# Sheet_1_2024-01-01_1.net
KiCad netlist of a schematic drawn in Altium Designer
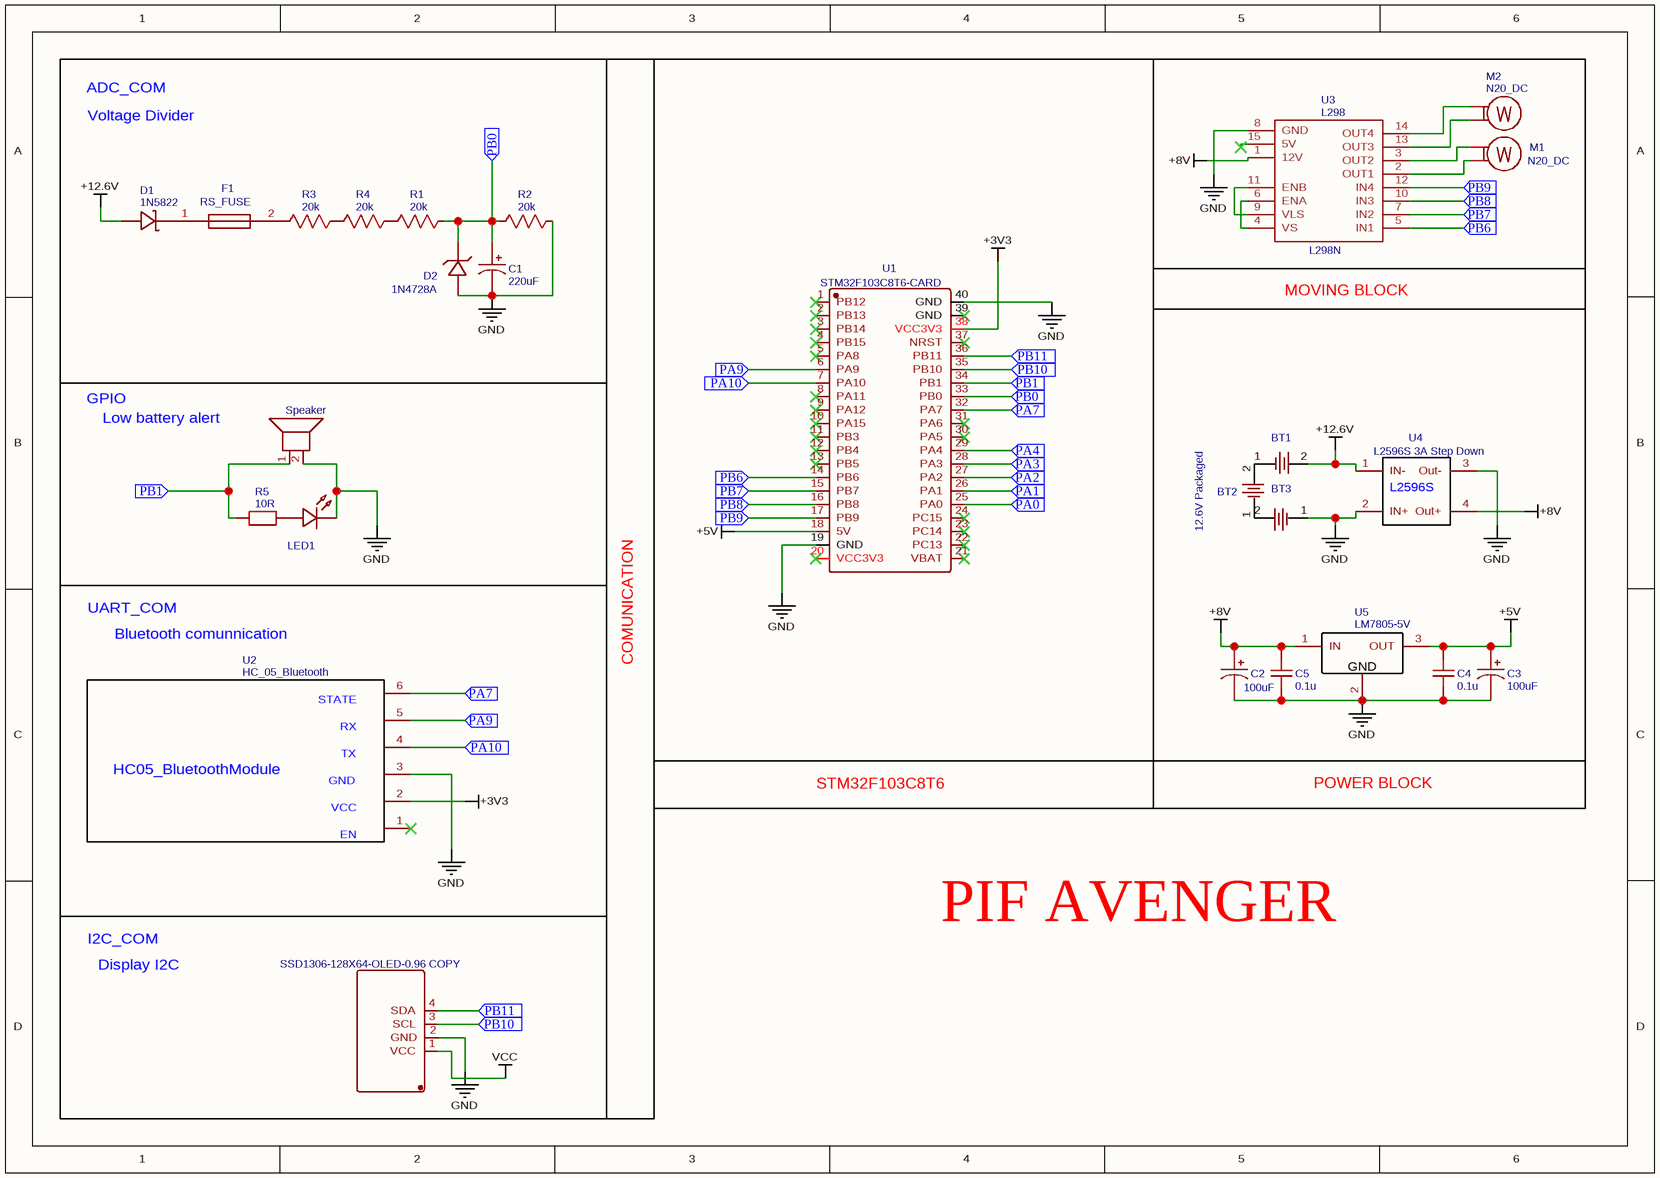
[diagram p0: Sheet_1_2024-01-01 (1).schdoc]

(export (version "E")
  (design (tool "Eeschema 10.0.6"))
  (components
    (comp (ref "BT1")
      (value "BH-18650-A1AJ006")
      (fields (field (name "MANUFACTURER") "MYOUNG(美阳)") (field (name "CONTRIBUTOR") "lcsc"))
      (libsource (lib "altium-import") (part "root_0_BH-18650-A1AJ006_"))
    )
    (comp (ref "BT2")
      (value "12.6V Packaged")
      (fields
        (field (name "MANUFACTURER") "MYOUNG(美阳)")
        (field (name "MANUFACTURER PART") "BH-18650-A1AJ006")
        (field (name "CONTRIBUTOR") "lcsc")
      )
      (libsource (lib "altium-import") (part "root_3_12.6V Packaged_"))
    )
    (comp (ref "BT3")
      (value "BH-18650-A1AJ006")
      (fields (field (name "MANUFACTURER") "MYOUNG(美阳)") (field (name "CONTRIBUTOR") "lcsc"))
      (libsource (lib "altium-import") (part "root_2_BH-18650-A1AJ006_"))
    )
    (comp (ref "C1")
      (value "220uF")
      (fields (field (name "CONTRIBUTOR") "LCEDA_Lib"))
      (libsource (lib "altium-import") (part "root_3_220uF_"))
    )
    (comp (ref "C2")
      (value "100uF")
      (fields (field (name "CONTRIBUTOR") "LCEDA_Lib"))
      (libsource (lib "altium-import") (part "root_3_100uF_"))
    )
    (comp (ref "C3")
      (value "100uF")
      (fields (field (name "CONTRIBUTOR") "LCEDA_Lib"))
      (libsource (lib "altium-import") (part "root_3_100uF_"))
    )
    (comp (ref "C4")
      (value "0.1u")
      (fields (field (name "CONTRIBUTOR") "LCEDA_Lib"))
      (libsource (lib "altium-import") (part "root_1_0.1u_"))
    )
    (comp (ref "C5")
      (value "0.1u")
      (fields (field (name "CONTRIBUTOR") "LCEDA_Lib"))
      (libsource (lib "altium-import") (part "root_1_0.1u_"))
    )
    (comp (ref "D1")
      (value "1N5822")
      (fields (field (name "MANUFACTURER") "MDD"))
      (libsource (lib "altium-import") (part "root_0_1N5822_"))
    )
    (comp (ref "D2")
      (value "1N4728A")
      (fields (field (name "MANUFACTURER") "onsemi(安森美)") (field (name "CONTRIBUTOR") "LCSC"))
      (libsource (lib "altium-import") (part "root_3_1N4728A_"))
    )
    (comp (ref "F1")
      (value "RS_FUSE")
      (fields (field (name "MANUFACTURER PART") "ResettableFuse-500mA") (field (name "CONTRIBUTOR") "LCSC"))
      (libsource (lib "altium-import") (part "root_0_RS_FUSE_"))
    )
    (comp (ref "LED1")
      (value "LED-0603_R")
      (fields
        (field (name "MANUFACTURER") "EVERLIGHT(台湾亿光)")
        (field (name "MANUFACTURER PART") "19-217/R6C-AL1M2VY/3T")
        (field (name "CONTRIBUTOR") "LCEDA_01")
      )
      (libsource (lib "altium-import") (part "root_0_LED-0603_R_"))
    )
    (comp (ref "LS1")
      (value "Speaker")
      (fields (field (name "CONTRIBUTOR") "virtualgt"))
      (libsource (lib "altium-import") (part "root_1_Speaker_"))
    )
    (comp (ref "M1")
      (value "N20_DC")
      (fields (field (name "CONTRIBUTOR") "crypt-pcb"))
      (libsource (lib "altium-import") (part "root_1_N20_DC_"))
    )
    (comp (ref "M2")
      (value "N20_DC")
      (fields (field (name "CONTRIBUTOR") "crypt-pcb"))
      (libsource (lib "altium-import") (part "root_1_N20_DC_"))
    )
    (comp (ref "PCB1")
      (value "SSD1306-128X64-OLED-0.96 COPY")
      (libsource (lib "altium-import") (part "root_2_SSD1306-128X64-OLED-0.96 COPY_"))
    )
    (comp (ref "R1")
      (value "20k")
      (fields (field (name "CONTRIBUTOR") "LCEDA_Lib"))
      (libsource (lib "altium-import") (part "root_0_20k_"))
    )
    (comp (ref "R2")
      (value "20k")
      (fields (field (name "CONTRIBUTOR") "LCEDA_Lib"))
      (libsource (lib "altium-import") (part "root_0_20k_"))
    )
    (comp (ref "R3")
      (value "20k")
      (fields (field (name "CONTRIBUTOR") "LCEDA_Lib"))
      (libsource (lib "altium-import") (part "root_0_20k_"))
    )
    (comp (ref "R4")
      (value "20k")
      (fields (field (name "CONTRIBUTOR") "LCEDA_Lib"))
      (libsource (lib "altium-import") (part "root_0_20k_"))
    )
    (comp (ref "R5")
      (value "10R")
      (fields (field (name "CONTRIBUTOR") "LCEDA_Lib"))
      (libsource (lib "altium-import") (part "root_0_10R_"))
    )
    (comp (ref "U1")
      (value "STM32F103C8T6-CARD")
      (fields (field (name "MANUFACTURER PART") "STM32F103C8T6-Card") (field (name "CONTRIBUTOR") "lcsc"))
      (libsource (lib "altium-import") (part "root_0_STM32F103C8T6-CARD_"))
    )
    (comp (ref "U2")
      (value "HC_05_Bluetooth")
      (fields (field (name "CONTRIBUTOR") "Crypt-PCB"))
      (libsource (lib "altium-import") (part "root_1_HC_05_Bluetooth_"))
    )
    (comp (ref "U3")
      (value "L298")
      (fields
        (field (name "MANUFACTURER PART") "L298N Driver")
        (field (name "CONTRIBUTOR") "huynhthienphu2492001")
      )
      (libsource (lib "altium-import") (part "root_2_L298_"))
    )
    (comp (ref "U4")
      (value "L2596S 3A Step Down")
      (fields (field (name "CONTRIBUTOR") "St1fT"))
      (libsource (lib "altium-import") (part "root_0_L2596S 3A Step Down_"))
    )
    (comp (ref "U5")
      (value "LM7805-5V")
      (fields (field (name "CONTRIBUTOR") "LCSC"))
      (libsource (lib "altium-import") (part "root_0_LM7805-5V_"))
    )
  )
  (nets
    (net (code "1") (name "+3V3") (class "Default")
      (node (ref "U1") (pin "38") (pinfunction "VCC3V3_38") (pintype "passive"))
      (node (ref "U2") (pin "2") (pinfunction "2_2") (pintype "passive"))
    )
    (net (code "2") (name "+5V") (class "Default")
      (node (ref "C3") (pin "1") (pinfunction "1_1") (pintype "passive"))
      (node (ref "C4") (pin "2") (pinfunction "2_2") (pintype "passive"))
      (node (ref "U1") (pin "18") (pinfunction "5V_18") (pintype "passive"))
      (node (ref "U5") (pin "3") (pinfunction "OUT_3") (pintype "passive"))
    )
    (net (code "3") (name "+8V") (class "Default")
      (node (ref "C2") (pin "1") (pinfunction "1_1") (pintype "passive"))
      (node (ref "C5") (pin "2") (pinfunction "2_2") (pintype "passive"))
      (node (ref "U3") (pin "1") (pinfunction "12V_1") (pintype "passive"))
      (node (ref "U4") (pin "4") (pinfunction "Out+_4") (pintype "passive"))
      (node (ref "U5") (pin "1") (pinfunction "IN_1") (pintype "passive"))
    )
    (net (code "4") (name "+12.6V") (class "Default")
      (node (ref "BT1") (pin "2") (pinfunction "2_2") (pintype "passive"))
      (node (ref "D1") (pin "1") (pinfunction "A_1") (pintype "passive"))
      (node (ref "U4") (pin "1") (pinfunction "IN-_1") (pintype "passive"))
    )
    (net (code "5") (name "/PA0") (class "Default")
      (node (ref "U1") (pin "25") (pinfunction "PA0_25") (pintype "passive"))
    )
    (net (code "6") (name "/PA1") (class "Default")
      (node (ref "U1") (pin "26") (pinfunction "PA1_26") (pintype "passive"))
    )
    (net (code "7") (name "/PA2") (class "Default")
      (node (ref "U1") (pin "27") (pinfunction "PA2_27") (pintype "passive"))
    )
    (net (code "8") (name "/PA3") (class "Default")
      (node (ref "U1") (pin "28") (pinfunction "PA3_28") (pintype "passive"))
    )
    (net (code "9") (name "/PA4") (class "Default")
      (node (ref "U1") (pin "29") (pinfunction "PA4_29") (pintype "passive"))
    )
    (net (code "10") (name "/PA7") (class "Default")
      (node (ref "U1") (pin "32") (pinfunction "PA7_32") (pintype "passive"))
      (node (ref "U2") (pin "6") (pinfunction "6_6") (pintype "passive"))
    )
    (net (code "11") (name "/PA9") (class "Default")
      (node (ref "U1") (pin "6") (pinfunction "PA9_6") (pintype "passive"))
      (node (ref "U2") (pin "5") (pinfunction "5_5") (pintype "passive"))
    )
    (net (code "12") (name "/PA10") (class "Default")
      (node (ref "U1") (pin "7") (pinfunction "PA10_7") (pintype "passive"))
      (node (ref "U2") (pin "4") (pinfunction "4_4") (pintype "passive"))
    )
    (net (code "13") (name "/PB0") (class "Default")
      (node (ref "C1") (pin "1") (pinfunction "1_1") (pintype "passive"))
      (node (ref "D2") (pin "1") (pinfunction "K_1") (pintype "passive"))
      (node (ref "R1") (pin "2") (pinfunction "2_2") (pintype "passive"))
      (node (ref "R2") (pin "1") (pinfunction "1_1") (pintype "passive"))
      (node (ref "U1") (pin "33") (pinfunction "PB0_33") (pintype "passive"))
    )
    (net (code "14") (name "/PB1") (class "Default")
      (node (ref "LS1") (pin "1") (pinfunction "1_1") (pintype "passive"))
      (node (ref "R5") (pin "1") (pinfunction "1_1") (pintype "passive"))
      (node (ref "U1") (pin "34") (pinfunction "PB1_34") (pintype "passive"))
    )
    (net (code "15") (name "/PB6") (class "Default")
      (node (ref "U1") (pin "14") (pinfunction "PB6_14") (pintype "passive"))
      (node (ref "U3") (pin "5") (pinfunction "IN1_5") (pintype "passive"))
    )
    (net (code "16") (name "/PB7") (class "Default")
      (node (ref "U1") (pin "15") (pinfunction "PB7_15") (pintype "passive"))
      (node (ref "U3") (pin "7") (pinfunction "IN2_7") (pintype "passive"))
    )
    (net (code "17") (name "/PB8") (class "Default")
      (node (ref "U1") (pin "16") (pinfunction "PB8_16") (pintype "passive"))
      (node (ref "U3") (pin "10") (pinfunction "IN3_10") (pintype "passive"))
    )
    (net (code "18") (name "/PB9") (class "Default")
      (node (ref "U1") (pin "17") (pinfunction "PB9_17") (pintype "passive"))
      (node (ref "U3") (pin "12") (pinfunction "IN4_12") (pintype "passive"))
    )
    (net (code "19") (name "/PB10") (class "Default")
      (node (ref "PCB1") (pin "3") (pinfunction "SCL_3") (pintype "passive"))
      (node (ref "U1") (pin "35") (pinfunction "PB10_35") (pintype "passive"))
    )
    (net (code "20") (name "/PB11") (class "Default")
      (node (ref "PCB1") (pin "4") (pinfunction "SDA_4") (pintype "passive"))
      (node (ref "U1") (pin "36") (pinfunction "PB11_36") (pintype "passive"))
    )
    (net (code "21") (name "GND") (class "Default")
      (node (ref "BT3") (pin "1") (pinfunction "1_1") (pintype "passive"))
      (node (ref "C1") (pin "2") (pinfunction "2_2") (pintype "passive"))
      (node (ref "C2") (pin "2") (pinfunction "2_2") (pintype "passive"))
      (node (ref "C3") (pin "2") (pinfunction "2_2") (pintype "passive"))
      (node (ref "C4") (pin "1") (pinfunction "1_1") (pintype "passive"))
      (node (ref "C5") (pin "1") (pinfunction "1_1") (pintype "passive"))
      (node (ref "D2") (pin "2") (pinfunction "A_2") (pintype "passive"))
      (node (ref "LED1") (pin "2") (pinfunction "2_2") (pintype "passive"))
      (node (ref "LS1") (pin "2") (pinfunction "2_2") (pintype "passive"))
      (node (ref "PCB1") (pin "2") (pinfunction "GND_2") (pintype "passive"))
      (node (ref "R2") (pin "2") (pinfunction "2_2") (pintype "passive"))
      (node (ref "U1") (pin "19") (pinfunction "GND_19") (pintype "passive"))
      (node (ref "U1") (pin "40") (pinfunction "GND_40") (pintype "passive"))
      (node (ref "U2") (pin "3") (pinfunction "3_3") (pintype "passive"))
      (node (ref "U3") (pin "8") (pinfunction "GND_8") (pintype "passive"))
      (node (ref "U4") (pin "2") (pinfunction "IN+_2") (pintype "passive"))
      (node (ref "U4") (pin "3") (pinfunction "Out-_3") (pintype "passive"))
      (node (ref "U5") (pin "2") (pinfunction "GND_2") (pintype "passive"))
    )
    (net (code "22") (name "Net-(BT1-Pad1)") (class "Default")
      (node (ref "BT1") (pin "1") (pinfunction "1_1") (pintype "passive"))
      (node (ref "BT2") (pin "2") (pinfunction "2_2") (pintype "passive"))
    )
    (net (code "23") (name "Net-(BT2-Pad1)") (class "Default")
      (node (ref "BT2") (pin "1") (pinfunction "1_1") (pintype "passive"))
      (node (ref "BT3") (pin "2") (pinfunction "2_2") (pintype "passive"))
    )
    (net (code "24") (name "Net-(D1-K)") (class "Default")
      (node (ref "D1") (pin "2") (pinfunction "K_2") (pintype "passive"))
      (node (ref "F1") (pin "1") (pinfunction "1_1") (pintype "passive"))
    )
    (net (code "25") (name "Net-(F1-Pad2)") (class "Default")
      (node (ref "F1") (pin "2") (pinfunction "2_2") (pintype "passive"))
      (node (ref "R3") (pin "1") (pinfunction "1_1") (pintype "passive"))
    )
    (net (code "26") (name "Net-(M1-+)") (class "Default")
      (node (ref "M1") (pin "2") (pinfunction "+_2") (pintype "passive"))
      (node (ref "U3") (pin "2") (pinfunction "OUT1_2") (pintype "passive"))
    )
    (net (code "27") (name "Net-(M1--)") (class "Default")
      (node (ref "M1") (pin "1") (pinfunction "-_1") (pintype "passive"))
      (node (ref "U3") (pin "3") (pinfunction "OUT2_3") (pintype "passive"))
    )
    (net (code "28") (name "Net-(M2-+)") (class "Default")
      (node (ref "M2") (pin "2") (pinfunction "+_2") (pintype "passive"))
      (node (ref "U3") (pin "13") (pinfunction "OUT3_13") (pintype "passive"))
    )
    (net (code "29") (name "Net-(M2--)") (class "Default")
      (node (ref "M2") (pin "1") (pinfunction "-_1") (pintype "passive"))
      (node (ref "U3") (pin "14") (pinfunction "OUT4_14") (pintype "passive"))
    )
    (net (code "30") (name "Net-(R1-Pad1)") (class "Default")
      (node (ref "R1") (pin "1") (pinfunction "1_1") (pintype "passive"))
      (node (ref "R4") (pin "2") (pinfunction "2_2") (pintype "passive"))
    )
    (net (code "31") (name "Net-(R3-Pad2)") (class "Default")
      (node (ref "R3") (pin "2") (pinfunction "2_2") (pintype "passive"))
      (node (ref "R4") (pin "1") (pinfunction "1_1") (pintype "passive"))
    )
    (net (code "32") (name "Net-(U3-ENA)") (class "Default")
      (node (ref "U3") (pin "4") (pinfunction "VS_4") (pintype "passive"))
      (node (ref "U3") (pin "6") (pinfunction "ENA_6") (pintype "passive"))
    )
    (net (code "33") (name "Net-(U3-ENB)") (class "Default")
      (node (ref "U3") (pin "11") (pinfunction "ENB_11") (pintype "passive"))
      (node (ref "U3") (pin "9") (pinfunction "VLS_9") (pintype "passive"))
    )
    (net (code "34") (name "VCC") (class "Default")
      (node (ref "PCB1") (pin "1") (pinfunction "VCC_1") (pintype "passive"))
    )
    (net (code "35") (name "unconnected-(LED1-Pad1)") (class "Default")
      (node (ref "LED1") (pin "1") (pinfunction "1_1") (pintype "passive"))
    )
    (net (code "36") (name "unconnected-(R5-Pad2)") (class "Default")
      (node (ref "R5") (pin "2") (pinfunction "2_2") (pintype "passive"))
    )
    (net (code "37") (name "unconnected-(U1-GND-Pad39)") (class "Default")
      (node (ref "U1") (pin "39") (pinfunction "GND_39") (pintype "passive+no_connect"))
    )
    (net (code "38") (name "unconnected-(U1-NRST-Pad37)") (class "Default")
      (node (ref "U1") (pin "37") (pinfunction "NRST_37") (pintype "passive+no_connect"))
    )
    (net (code "39") (name "unconnected-(U1-PA5-Pad30)") (class "Default")
      (node (ref "U1") (pin "30") (pinfunction "PA5_30") (pintype "passive+no_connect"))
    )
    (net (code "40") (name "unconnected-(U1-PA6-Pad31)") (class "Default")
      (node (ref "U1") (pin "31") (pinfunction "PA6_31") (pintype "passive+no_connect"))
    )
    (net (code "41") (name "unconnected-(U1-PA8-Pad5)") (class "Default")
      (node (ref "U1") (pin "5") (pinfunction "PA8_5") (pintype "passive+no_connect"))
    )
    (net (code "42") (name "unconnected-(U1-PA11-Pad8)") (class "Default")
      (node (ref "U1") (pin "8") (pinfunction "PA11_8") (pintype "passive+no_connect"))
    )
    (net (code "43") (name "unconnected-(U1-PA12-Pad9)") (class "Default")
      (node (ref "U1") (pin "9") (pinfunction "PA12_9") (pintype "passive+no_connect"))
    )
    (net (code "44") (name "unconnected-(U1-PA15-Pad10)") (class "Default")
      (node (ref "U1") (pin "10") (pinfunction "PA15_10") (pintype "passive+no_connect"))
    )
    (net (code "45") (name "unconnected-(U1-PB3-Pad11)") (class "Default")
      (node (ref "U1") (pin "11") (pinfunction "PB3_11") (pintype "passive+no_connect"))
    )
    (net (code "46") (name "unconnected-(U1-PB4-Pad12)") (class "Default")
      (node (ref "U1") (pin "12") (pinfunction "PB4_12") (pintype "passive+no_connect"))
    )
    (net (code "47") (name "unconnected-(U1-PB5-Pad13)") (class "Default")
      (node (ref "U1") (pin "13") (pinfunction "PB5_13") (pintype "passive+no_connect"))
    )
    (net (code "48") (name "unconnected-(U1-PB12-Pad1)") (class "Default")
      (node (ref "U1") (pin "1") (pinfunction "PB12_1") (pintype "passive+no_connect"))
    )
    (net (code "49") (name "unconnected-(U1-PB13-Pad2)") (class "Default")
      (node (ref "U1") (pin "2") (pinfunction "PB13_2") (pintype "passive+no_connect"))
    )
    (net (code "50") (name "unconnected-(U1-PB14-Pad3)") (class "Default")
      (node (ref "U1") (pin "3") (pinfunction "PB14_3") (pintype "passive+no_connect"))
    )
    (net (code "51") (name "unconnected-(U1-PB15-Pad4)") (class "Default")
      (node (ref "U1") (pin "4") (pinfunction "PB15_4") (pintype "passive+no_connect"))
    )
    (net (code "52") (name "unconnected-(U1-PC13-Pad22)") (class "Default")
      (node (ref "U1") (pin "22") (pinfunction "PC13_22") (pintype "passive+no_connect"))
    )
    (net (code "53") (name "unconnected-(U1-PC14-Pad23)") (class "Default")
      (node (ref "U1") (pin "23") (pinfunction "PC14_23") (pintype "passive+no_connect"))
    )
    (net (code "54") (name "unconnected-(U1-PC15-Pad24)") (class "Default")
      (node (ref "U1") (pin "24") (pinfunction "PC15_24") (pintype "passive+no_connect"))
    )
    (net (code "55") (name "unconnected-(U1-VBAT-Pad21)") (class "Default")
      (node (ref "U1") (pin "21") (pinfunction "VBAT_21") (pintype "passive+no_connect"))
    )
    (net (code "56") (name "unconnected-(U1-VCC3V3-Pad20)") (class "Default")
      (node (ref "U1") (pin "20") (pinfunction "VCC3V3_20") (pintype "passive+no_connect"))
    )
    (net (code "57") (name "unconnected-(U2-Pad1)") (class "Default")
      (node (ref "U2") (pin "1") (pinfunction "1_1") (pintype "passive+no_connect"))
    )
    (net (code "58") (name "unconnected-(U3-5V-Pad15)") (class "Default")
      (node (ref "U3") (pin "15") (pinfunction "5V_15") (pintype "passive+no_connect"))
    )
  )
)
